# LCD.net
KiCad netlist of a schematic drawn in Altium Designer
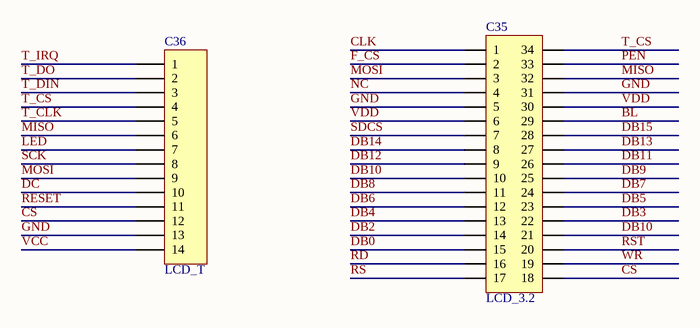
[diagram p0: LCD.SchDoc]

(export (version "E")
  (design (tool "Eeschema 10.0.6"))
  (components
    (comp (ref "C35")
      (value "LCD_3.2")
      (footprint "JP17-C2T")
      (description "WR-PHD 2.54 mm Dual Socket Header")
      (fields
        (field (name "MANUFACTURER") "Würth Elektronik eiSos GmbH")
        (field (name "PARTNO") "61303421821")
        (field (name "CREATED BY") "Karrer Zheng")
      )
      (libsource (lib "Main") (part "JP17x2"))
    )
    (comp (ref "C36")
      (value "LCD_T")
      (footprint "JP14-C1T")
      (description "WR-PHD 2.54 mm Angled Socket Header")
      (fields
        (field (name "MANUFACTURER") "Würth Elektronik eiSos GmbH")
        (field (name "PARTNO") "613014143121")
        (field (name "CREATED BY") "Karrer Zheng")
      )
      (libsource (lib "Main") (part "JP14"))
    )
  )
  (nets
    (net (code "1") (name "/BL") (class "Default")
      (node (ref "C35") (pin "29") (pinfunction "29_29") (pintype "passive"))
    )
    (net (code "2") (name "/CLK") (class "Default")
      (node (ref "C35") (pin "1") (pinfunction "1_1") (pintype "passive"))
    )
    (net (code "3") (name "/CS") (class "Default")
      (node (ref "C35") (pin "18") (pinfunction "18_18") (pintype "passive"))
      (node (ref "C36") (pin "12") (pinfunction "12_12") (pintype "passive"))
    )
    (net (code "4") (name "/DB0") (class "Default")
      (node (ref "C35") (pin "15") (pinfunction "15_15") (pintype "passive"))
    )
    (net (code "5") (name "/DB2") (class "Default")
      (node (ref "C35") (pin "14") (pinfunction "14_14") (pintype "passive"))
    )
    (net (code "6") (name "/DB3") (class "Default")
      (node (ref "C35") (pin "22") (pinfunction "22_22") (pintype "passive"))
    )
    (net (code "7") (name "/DB4") (class "Default")
      (node (ref "C35") (pin "13") (pinfunction "13_13") (pintype "passive"))
    )
    (net (code "8") (name "/DB5") (class "Default")
      (node (ref "C35") (pin "23") (pinfunction "23_23") (pintype "passive"))
    )
    (net (code "9") (name "/DB6") (class "Default")
      (node (ref "C35") (pin "12") (pinfunction "12_12") (pintype "passive"))
    )
    (net (code "10") (name "/DB7") (class "Default")
      (node (ref "C35") (pin "24") (pinfunction "24_24") (pintype "passive"))
    )
    (net (code "11") (name "/DB8") (class "Default")
      (node (ref "C35") (pin "11") (pinfunction "11_11") (pintype "passive"))
    )
    (net (code "12") (name "/DB9") (class "Default")
      (node (ref "C35") (pin "25") (pinfunction "25_25") (pintype "passive"))
    )
    (net (code "13") (name "/DB10") (class "Default")
      (node (ref "C35") (pin "10") (pinfunction "10_10") (pintype "passive"))
      (node (ref "C35") (pin "21") (pinfunction "21_21") (pintype "passive"))
    )
    (net (code "14") (name "/DB11") (class "Default")
      (node (ref "C35") (pin "26") (pinfunction "26_26") (pintype "passive"))
    )
    (net (code "15") (name "/DB12") (class "Default")
      (node (ref "C35") (pin "9") (pinfunction "9_9") (pintype "passive"))
    )
    (net (code "16") (name "/DB13") (class "Default")
      (node (ref "C35") (pin "27") (pinfunction "27_27") (pintype "passive"))
    )
    (net (code "17") (name "/DB14") (class "Default")
      (node (ref "C35") (pin "8") (pinfunction "8_8") (pintype "passive"))
    )
    (net (code "18") (name "/DB15") (class "Default")
      (node (ref "C35") (pin "28") (pinfunction "28_28") (pintype "passive"))
    )
    (net (code "19") (name "/DC") (class "Default")
      (node (ref "C36") (pin "10") (pinfunction "10_10") (pintype "passive"))
    )
    (net (code "20") (name "/F_CS") (class "Default")
      (node (ref "C35") (pin "2") (pinfunction "2_2") (pintype "passive"))
    )
    (net (code "21") (name "/GND") (class "Default")
      (node (ref "C35") (pin "31") (pinfunction "31_31") (pintype "passive"))
      (node (ref "C35") (pin "5") (pinfunction "5_5") (pintype "passive"))
      (node (ref "C36") (pin "13") (pinfunction "13_13") (pintype "passive"))
    )
    (net (code "22") (name "/LED") (class "Default")
      (node (ref "C36") (pin "7") (pinfunction "7_7") (pintype "passive"))
    )
    (net (code "23") (name "/MISO") (class "Default")
      (node (ref "C35") (pin "32") (pinfunction "32_32") (pintype "passive"))
      (node (ref "C36") (pin "6") (pinfunction "6_6") (pintype "passive"))
    )
    (net (code "24") (name "/MOSI") (class "Default")
      (node (ref "C35") (pin "3") (pinfunction "3_3") (pintype "passive"))
      (node (ref "C36") (pin "9") (pinfunction "9_9") (pintype "passive"))
    )
    (net (code "25") (name "/NC") (class "Default")
      (node (ref "C35") (pin "4") (pinfunction "4_4") (pintype "passive"))
    )
    (net (code "26") (name "/PEN") (class "Default")
      (node (ref "C35") (pin "33") (pinfunction "33_33") (pintype "passive"))
    )
    (net (code "27") (name "/RD") (class "Default")
      (node (ref "C35") (pin "16") (pinfunction "16_16") (pintype "passive"))
    )
    (net (code "28") (name "/RESET") (class "Default")
      (node (ref "C36") (pin "11") (pinfunction "11_11") (pintype "passive"))
    )
    (net (code "29") (name "/RS") (class "Default")
      (node (ref "C35") (pin "17") (pinfunction "17_17") (pintype "passive"))
    )
    (net (code "30") (name "/RST") (class "Default")
      (node (ref "C35") (pin "20") (pinfunction "20_20") (pintype "passive"))
    )
    (net (code "31") (name "/SCK") (class "Default")
      (node (ref "C36") (pin "8") (pinfunction "8_8") (pintype "passive"))
    )
    (net (code "32") (name "/SDCS") (class "Default")
      (node (ref "C35") (pin "7") (pinfunction "7_7") (pintype "passive"))
    )
    (net (code "33") (name "/T_CLK") (class "Default")
      (node (ref "C36") (pin "5") (pinfunction "5_5") (pintype "passive"))
    )
    (net (code "34") (name "/T_CS") (class "Default")
      (node (ref "C35") (pin "34") (pinfunction "34_34") (pintype "passive"))
      (node (ref "C36") (pin "4") (pinfunction "4_4") (pintype "passive"))
    )
    (net (code "35") (name "/T_DIN") (class "Default")
      (node (ref "C36") (pin "3") (pinfunction "3_3") (pintype "passive"))
    )
    (net (code "36") (name "/T_DO") (class "Default")
      (node (ref "C36") (pin "2") (pinfunction "2_2") (pintype "passive"))
    )
    (net (code "37") (name "/T_IRQ") (class "Default")
      (node (ref "C36") (pin "1") (pinfunction "1_1") (pintype "passive"))
    )
    (net (code "38") (name "/VCC") (class "Default")
      (node (ref "C36") (pin "14") (pinfunction "14_14") (pintype "passive"))
    )
    (net (code "39") (name "/VDD") (class "Default")
      (node (ref "C35") (pin "30") (pinfunction "30_30") (pintype "passive"))
      (node (ref "C35") (pin "6") (pinfunction "6_6") (pintype "passive"))
    )
    (net (code "40") (name "/WR") (class "Default")
      (node (ref "C35") (pin "19") (pinfunction "19_19") (pintype "passive"))
    )
  )
)
